# scHnRk_3.net
KiCad netlist of a schematic drawn in EAGLE
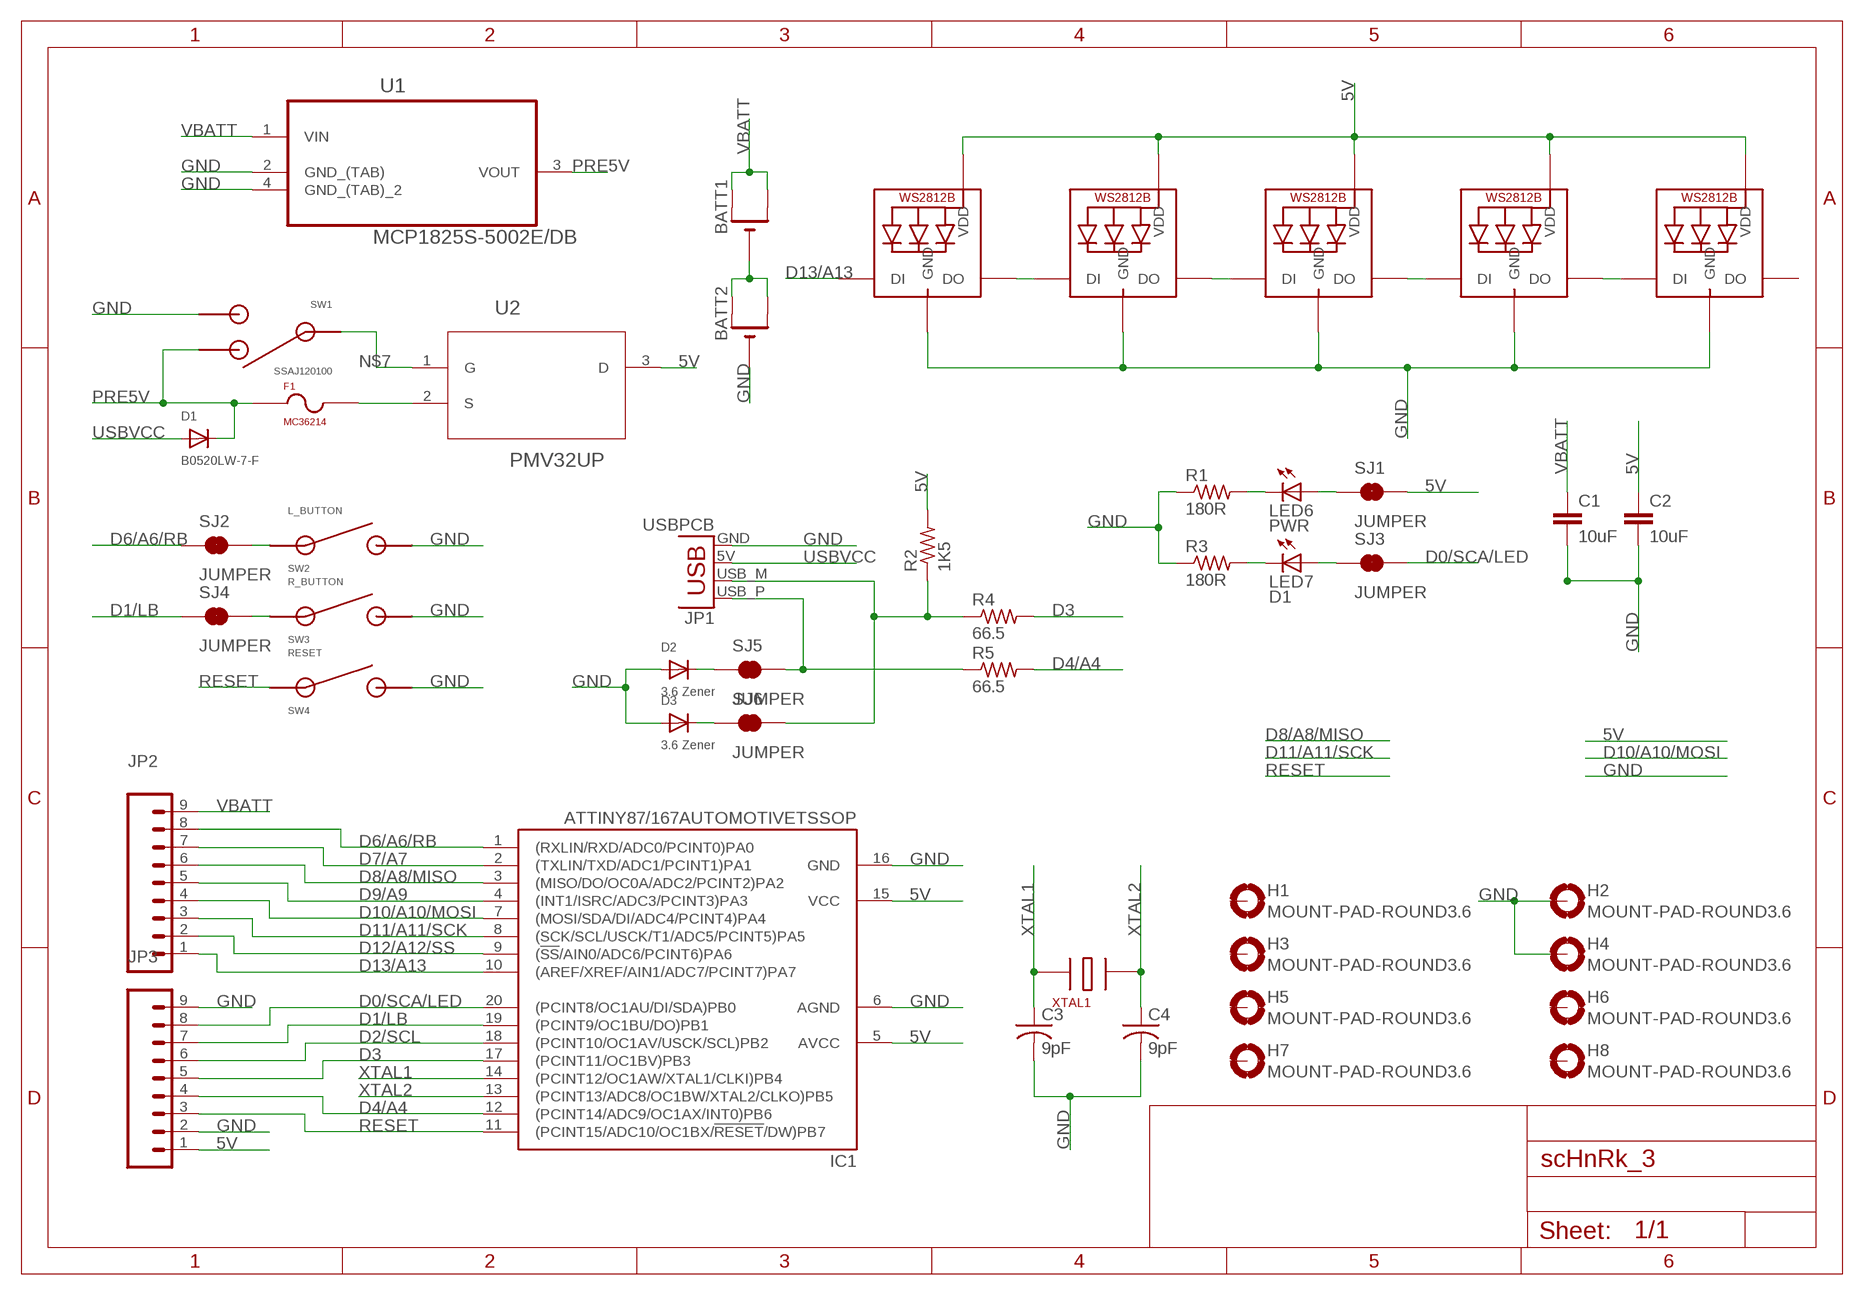
[diagram p0: schematic, sheet 1]

(export (version "E")
  (design (tool "Eeschema 10.0.6"))
  (components
    (comp (ref "BATT1")
      (value "CR2032SMT")
      (footprint "eagle-import:CR2032-SMD")
      (libsource (lib "eagle-import") (part "CR2032SMT"))
    )
    (comp (ref "BATT2")
      (value "CR2032SMT")
      (footprint "eagle-import:CR2032-SMD")
      (libsource (lib "eagle-import") (part "CR2032SMT"))
    )
    (comp (ref "C1")
      (value "10uF")
      (footprint "eagle-import:0805")
      (libsource (lib "eagle-import") (part "CAP0805"))
    )
    (comp (ref "C2")
      (value "10uF")
      (footprint "eagle-import:0805")
      (libsource (lib "eagle-import") (part "CAP0805"))
    )
    (comp (ref "C3")
      (value "9pF")
      (footprint "eagle-import:C0603K")
      (libsource (lib "eagle-import") (part "C-USC0603K"))
    )
    (comp (ref "C4")
      (value "9pF")
      (footprint "eagle-import:C0603K")
      (libsource (lib "eagle-import") (part "C-USC0603K"))
    )
    (comp (ref "D1")
      (value "B0520LW-7-F")
      (footprint "eagle-import:SOD-123")
      (libsource (lib "eagle-import") (part "DIODESOD-123"))
    )
    (comp (ref "D2")
      (value "3.6 Zener")
      (footprint "eagle-import:SOD-523")
      (libsource (lib "eagle-import") (part "DIODESOD-523"))
    )
    (comp (ref "D3")
      (value "3.6 Zener")
      (footprint "eagle-import:SOD-523")
      (libsource (lib "eagle-import") (part "DIODESOD-523"))
    )
    (comp (ref "F1")
      (value "MC36214")
      (footprint "eagle-import:MC36214")
      (libsource (lib "eagle-import") (part "MC36214"))
    )
    (comp (ref "H1")
      (value "MOUNT-PAD-ROUND3.6")
      (footprint "eagle-import:3,6-PAD")
      (libsource (lib "eagle-import") (part "MOUNT-PAD-ROUND3.6"))
    )
    (comp (ref "H2")
      (value "MOUNT-PAD-ROUND3.6")
      (footprint "eagle-import:3,6-PAD")
      (libsource (lib "eagle-import") (part "MOUNT-PAD-ROUND3.6"))
    )
    (comp (ref "H3")
      (value "MOUNT-PAD-ROUND3.6")
      (footprint "eagle-import:3,6-PAD")
      (libsource (lib "eagle-import") (part "MOUNT-PAD-ROUND3.6"))
    )
    (comp (ref "H4")
      (value "MOUNT-PAD-ROUND3.6")
      (footprint "eagle-import:3,6-PAD")
      (libsource (lib "eagle-import") (part "MOUNT-PAD-ROUND3.6"))
    )
    (comp (ref "H5")
      (value "MOUNT-PAD-ROUND3.6")
      (footprint "eagle-import:3,6-PAD")
      (libsource (lib "eagle-import") (part "MOUNT-PAD-ROUND3.6"))
    )
    (comp (ref "H6")
      (value "MOUNT-PAD-ROUND3.6")
      (footprint "eagle-import:3,6-PAD")
      (libsource (lib "eagle-import") (part "MOUNT-PAD-ROUND3.6"))
    )
    (comp (ref "H7")
      (value "MOUNT-PAD-ROUND3.6")
      (footprint "eagle-import:3,6-PAD")
      (libsource (lib "eagle-import") (part "MOUNT-PAD-ROUND3.6"))
    )
    (comp (ref "H8")
      (value "MOUNT-PAD-ROUND3.6")
      (footprint "eagle-import:3,6-PAD")
      (libsource (lib "eagle-import") (part "MOUNT-PAD-ROUND3.6"))
    )
    (comp (ref "IC1")
      (value "ATTINY87/167AUTOMOTIVETSSOP")
      (footprint "eagle-import:TSSOP20")
      (libsource (lib "eagle-import") (part "ATTINY87/167AUTOMOTIVETSSOP"))
    )
    (comp (ref "JP1")
      (value "USBPCB")
      (footprint "eagle-import:USB-A-PCB")
      (libsource (lib "eagle-import") (part "USBPCB"))
    )
    (comp (ref "JP2")
      (value "M09")
      (footprint "eagle-import:1X09")
      (libsource (lib "eagle-import") (part "M09"))
    )
    (comp (ref "JP3")
      (value "M09")
      (footprint "eagle-import:1X09")
      (libsource (lib "eagle-import") (part "M09"))
    )
    (comp (ref "LED1")
      (value "WS2812B5050")
      (footprint "eagle-import:WS2812B")
      (libsource (lib "eagle-import") (part "WS2812B5050"))
    )
    (comp (ref "LED2")
      (value "WS2812B5050")
      (footprint "eagle-import:WS2812B")
      (libsource (lib "eagle-import") (part "WS2812B5050"))
    )
    (comp (ref "LED3")
      (value "WS2812B5050")
      (footprint "eagle-import:WS2812B")
      (libsource (lib "eagle-import") (part "WS2812B5050"))
    )
    (comp (ref "LED4")
      (value "WS2812B5050")
      (footprint "eagle-import:WS2812B")
      (libsource (lib "eagle-import") (part "WS2812B5050"))
    )
    (comp (ref "LED5")
      (value "WS2812B5050")
      (footprint "eagle-import:WS2812B")
      (libsource (lib "eagle-import") (part "WS2812B5050"))
    )
    (comp (ref "LED6")
      (value "PWR")
      (footprint "eagle-import:CHIPLED_0603")
      (libsource (lib "eagle-import") (part "LEDCHIPLED_0603"))
    )
    (comp (ref "LED7")
      (value "D1")
      (footprint "eagle-import:CHIPLED_0603")
      (libsource (lib "eagle-import") (part "LEDCHIPLED_0603"))
    )
    (comp (ref "R1")
      (value "180R")
      (footprint "eagle-import:R0603")
      (libsource (lib "eagle-import") (part "R-US_R0603"))
    )
    (comp (ref "R2")
      (value "1K5")
      (footprint "eagle-import:R0603")
      (libsource (lib "eagle-import") (part "R-US_R0603"))
    )
    (comp (ref "R3")
      (value "180R")
      (footprint "eagle-import:R0603")
      (libsource (lib "eagle-import") (part "R-US_R0603"))
    )
    (comp (ref "R4")
      (value "66.5")
      (footprint "eagle-import:R0603")
      (libsource (lib "eagle-import") (part "R-US_R0603"))
    )
    (comp (ref "R5")
      (value "66.5")
      (footprint "eagle-import:R0603")
      (libsource (lib "eagle-import") (part "R-US_R0603"))
    )
    (comp (ref "SJ1")
      (value "JUMPER")
      (footprint "eagle-import:PAD-JUMPER-2-NC_BY_TRACE_YES_SILK")
      (libsource (lib "eagle-import") (part "JUMPER-PAD-2-NC_BY_TRACE"))
    )
    (comp (ref "SJ2")
      (value "JUMPER")
      (footprint "eagle-import:PAD-JUMPER-2-NC_BY_TRACE_YES_SILK")
      (libsource (lib "eagle-import") (part "JUMPER-PAD-2-NC_BY_TRACE"))
    )
    (comp (ref "SJ3")
      (value "JUMPER")
      (footprint "eagle-import:PAD-JUMPER-2-NC_BY_TRACE_YES_SILK")
      (libsource (lib "eagle-import") (part "JUMPER-PAD-2-NC_BY_TRACE"))
    )
    (comp (ref "SJ4")
      (value "JUMPER")
      (footprint "eagle-import:PAD-JUMPER-2-NC_BY_TRACE_YES_SILK")
      (libsource (lib "eagle-import") (part "JUMPER-PAD-2-NC_BY_TRACE"))
    )
    (comp (ref "SJ5")
      (value "JUMPER")
      (footprint "eagle-import:PAD-JUMPER-2-NC_BY_TRACE_YES_SILK")
      (libsource (lib "eagle-import") (part "JUMPER-PAD-2-NC_BY_TRACE"))
    )
    (comp (ref "SJ6")
      (value "JUMPER")
      (footprint "eagle-import:PAD-JUMPER-2-NC_BY_TRACE_YES_SILK")
      (libsource (lib "eagle-import") (part "JUMPER-PAD-2-NC_BY_TRACE"))
    )
    (comp (ref "SW1")
      (value "SSAJ120100")
      (footprint "eagle-import:SSAJ120100")
      (libsource (lib "eagle-import") (part "SSAJ120100"))
    )
    (comp (ref "SW2")
      (value "L_BUTTON")
      (footprint "eagle-import:SKRBAGE010")
      (libsource (lib "eagle-import") (part "SKRBAGE010"))
    )
    (comp (ref "SW3")
      (value "R_BUTTON")
      (footprint "eagle-import:SKRBAGE010")
      (libsource (lib "eagle-import") (part "SKRBAGE010"))
    )
    (comp (ref "SW4")
      (value "RESET")
      (footprint "eagle-import:SKRBAGE010")
      (libsource (lib "eagle-import") (part "SKRBAGE010"))
    )
    (comp (ref "U1")
      (value "MCP1825S-5002E/DB")
      (footprint "eagle-import:SOT230P700X180-4N")
      (libsource (lib "eagle-import") (part "MCP1825S-5002E/DB"))
    )
    (comp (ref "U2")
      (value "PMV32UP")
      (footprint "eagle-import:SOT95P230X110-3N")
      (libsource (lib "eagle-import") (part "PMV32UP"))
    )
    (comp (ref "XTAL1")
      (value "16MHZ-2467444")
      (footprint "eagle-import:16MHZ-2467444")
      (libsource (lib "eagle-import") (part "16MHZ-2467444"))
    )
  )
  (nets
    (net (code "1") (name "/5V") (class "Default")
      (node (ref "C2") (pin "1") (pinfunction "1_1") (pintype "passive"))
      (node (ref "IC1") (pin "15") (pinfunction "VCC_15") (pintype "power_in"))
      (node (ref "IC1") (pin "5") (pinfunction "AVCC_5") (pintype "bidirectional"))
      (node (ref "JP3") (pin "1") (pinfunction "1_1") (pintype "passive"))
      (node (ref "LED1") (pin "1-VDD") (pinfunction "VDD_1-VDD") (pintype "power_in"))
      (node (ref "LED2") (pin "1-VDD") (pinfunction "VDD_1-VDD") (pintype "power_in"))
      (node (ref "LED3") (pin "1-VDD") (pinfunction "VDD_1-VDD") (pintype "power_in"))
      (node (ref "LED4") (pin "1-VDD") (pinfunction "VDD_1-VDD") (pintype "power_in"))
      (node (ref "LED5") (pin "1-VDD") (pinfunction "VDD_1-VDD") (pintype "power_in"))
      (node (ref "R2") (pin "2") (pinfunction "2_2") (pintype "passive"))
      (node (ref "SJ1") (pin "2") (pinfunction "2_2") (pintype "passive"))
      (node (ref "U2") (pin "3") (pinfunction "D_3") (pintype "passive"))
    )
    (net (code "2") (name "/D0{slash}SCA{slash}LED") (class "Default")
      (node (ref "IC1") (pin "20") (pinfunction "(PCINT8/OC1AU/DI/SDA)PB0_20") (pintype "bidirectional"))
      (node (ref "JP3") (pin "8") (pinfunction "8_8") (pintype "passive"))
      (node (ref "SJ3") (pin "2") (pinfunction "2_2") (pintype "passive"))
    )
    (net (code "3") (name "/D1{slash}LB") (class "Default")
      (node (ref "IC1") (pin "19") (pinfunction "(PCINT9/OC1BU/DO)PB1_19") (pintype "bidirectional"))
      (node (ref "JP3") (pin "7") (pinfunction "7_7") (pintype "passive"))
      (node (ref "SJ4") (pin "1") (pinfunction "1_1") (pintype "passive"))
    )
    (net (code "4") (name "/D2{slash}SCL") (class "Default")
      (node (ref "IC1") (pin "18") (pinfunction "(PCINT10/OC1AV/USCK/SCL)PB2_18") (pintype "bidirectional"))
      (node (ref "JP3") (pin "6") (pinfunction "6_6") (pintype "passive"))
    )
    (net (code "5") (name "/D3") (class "Default")
      (node (ref "IC1") (pin "17") (pinfunction "(PCINT11/OC1BV)PB3_17") (pintype "bidirectional"))
      (node (ref "JP3") (pin "5") (pinfunction "5_5") (pintype "passive"))
      (node (ref "R4") (pin "2") (pinfunction "2_2") (pintype "passive"))
    )
    (net (code "6") (name "/D4{slash}A4") (class "Default")
      (node (ref "IC1") (pin "12") (pinfunction "(PCINT14/ADC9/OC1AX/INT0)PB6_12") (pintype "bidirectional"))
      (node (ref "JP3") (pin "4") (pinfunction "4_4") (pintype "passive"))
      (node (ref "R5") (pin "2") (pinfunction "2_2") (pintype "passive"))
    )
    (net (code "7") (name "/D6{slash}A6{slash}RB") (class "Default")
      (node (ref "IC1") (pin "1") (pinfunction "(RXLIN/RXD/ADC0/PCINT0)PA0_1") (pintype "bidirectional"))
      (node (ref "JP2") (pin "8") (pinfunction "8_8") (pintype "passive"))
      (node (ref "SJ2") (pin "1") (pinfunction "1_1") (pintype "passive"))
    )
    (net (code "8") (name "/D7{slash}A7") (class "Default")
      (node (ref "IC1") (pin "2") (pinfunction "(TXLIN/TXD/ADC1/PCINT1)PA1_2") (pintype "bidirectional"))
      (node (ref "JP2") (pin "7") (pinfunction "7_7") (pintype "passive"))
    )
    (net (code "9") (name "/D8{slash}A8{slash}MISO") (class "Default")
      (node (ref "IC1") (pin "3") (pinfunction "(MISO/DO/OC0A/ADC2/PCINT2)PA2_3") (pintype "bidirectional"))
      (node (ref "JP2") (pin "6") (pinfunction "6_6") (pintype "passive"))
    )
    (net (code "10") (name "/D9{slash}A9") (class "Default")
      (node (ref "IC1") (pin "4") (pinfunction "(INT1/ISRC/ADC3/PCINT3)PA3_4") (pintype "bidirectional"))
      (node (ref "JP2") (pin "5") (pinfunction "5_5") (pintype "passive"))
    )
    (net (code "11") (name "/D10{slash}A10{slash}MOSI") (class "Default")
      (node (ref "IC1") (pin "7") (pinfunction "(MOSI/SDA/DI/ADC4/PCINT4)PA4_7") (pintype "bidirectional"))
      (node (ref "JP2") (pin "4") (pinfunction "4_4") (pintype "passive"))
    )
    (net (code "12") (name "/D11{slash}A11{slash}SCK") (class "Default")
      (node (ref "IC1") (pin "8") (pinfunction "(SCK/SCL/USCK/T1/ADC5/PCINT5)PA5_8") (pintype "bidirectional"))
      (node (ref "JP2") (pin "3") (pinfunction "3_3") (pintype "passive"))
    )
    (net (code "13") (name "/D12{slash}A12{slash}SS") (class "Default")
      (node (ref "IC1") (pin "9") (pinfunction "(~{SS}/AIN0/ADC6/PCINT6)PA6_9") (pintype "bidirectional"))
      (node (ref "JP2") (pin "2") (pinfunction "2_2") (pintype "passive"))
    )
    (net (code "14") (name "/D13{slash}A13") (class "Default")
      (node (ref "IC1") (pin "10") (pinfunction "(AREF/XREF/AIN1/ADC7/PCINT7)PA7_10") (pintype "bidirectional"))
      (node (ref "JP2") (pin "1") (pinfunction "1_1") (pintype "passive"))
      (node (ref "LED1") (pin "4-DIN") (pinfunction "DI_4-DIN") (pintype "input"))
    )
    (net (code "15") (name "/GND") (class "Default")
      (node (ref "BATT2") (pin "-") (pinfunction "-_-") (pintype "passive"))
      (node (ref "C1") (pin "2") (pinfunction "2_2") (pintype "passive"))
      (node (ref "C2") (pin "2") (pinfunction "2_2") (pintype "passive"))
      (node (ref "C3") (pin "2") (pinfunction "2_2") (pintype "passive"))
      (node (ref "C4") (pin "2") (pinfunction "2_2") (pintype "passive"))
      (node (ref "D2") (pin "A") (pinfunction "A_A") (pintype "passive"))
      (node (ref "D3") (pin "A") (pinfunction "A_A") (pintype "passive"))
      (node (ref "H2") (pin "B3,6") (pinfunction "MOUNT_B3,6") (pintype "passive"))
      (node (ref "H4") (pin "B3,6") (pinfunction "MOUNT_B3,6") (pintype "passive"))
      (node (ref "IC1") (pin "16") (pinfunction "GND_16") (pintype "power_in"))
      (node (ref "IC1") (pin "6") (pinfunction "AGND_6") (pintype "bidirectional"))
      (node (ref "JP1") (pin "GND") (pinfunction "GND_GND") (pintype "bidirectional"))
      (node (ref "JP3") (pin "2") (pinfunction "2_2") (pintype "passive"))
      (node (ref "JP3") (pin "9") (pinfunction "9_9") (pintype "passive"))
      (node (ref "LED1") (pin "3-GND") (pinfunction "GND_3-GND") (pintype "power_in"))
      (node (ref "LED2") (pin "3-GND") (pinfunction "GND_3-GND") (pintype "power_in"))
      (node (ref "LED3") (pin "3-GND") (pinfunction "GND_3-GND") (pintype "power_in"))
      (node (ref "LED4") (pin "3-GND") (pinfunction "GND_3-GND") (pintype "power_in"))
      (node (ref "LED5") (pin "3-GND") (pinfunction "GND_3-GND") (pintype "power_in"))
      (node (ref "R1") (pin "1") (pinfunction "1_1") (pintype "passive"))
      (node (ref "R3") (pin "1") (pinfunction "1_1") (pintype "passive"))
      (node (ref "SW1") (pin "P$2") (pinfunction "P$2_P$2") (pintype "bidirectional"))
      (node (ref "SW2") (pin "P$2") (pinfunction "P$2_P$2") (pintype "bidirectional"))
      (node (ref "SW2") (pin "P$4") (pinfunction "P$2_P$4") (pintype "bidirectional"))
      (node (ref "SW3") (pin "P$2") (pinfunction "P$2_P$2") (pintype "bidirectional"))
      (node (ref "SW3") (pin "P$4") (pinfunction "P$2_P$4") (pintype "bidirectional"))
      (node (ref "SW4") (pin "P$2") (pinfunction "P$2_P$2") (pintype "bidirectional"))
      (node (ref "SW4") (pin "P$4") (pinfunction "P$2_P$4") (pintype "bidirectional"))
      (node (ref "U1") (pin "2") (pinfunction "GND_(TAB)_2") (pintype "passive"))
      (node (ref "U1") (pin "4") (pinfunction "GND_(TAB)_2_4") (pintype "passive"))
    )
    (net (code "16") (name "/N$7") (class "Default")
      (node (ref "SW1") (pin "P$C") (pinfunction "P$C_P$C") (pintype "bidirectional"))
      (node (ref "U2") (pin "1") (pinfunction "G_1") (pintype "passive"))
    )
    (net (code "17") (name "/PRE5V") (class "Default")
      (node (ref "D1") (pin "C") (pinfunction "C_C") (pintype "passive"))
      (node (ref "F1") (pin "P$1") (pinfunction "P$1_P$1") (pintype "bidirectional"))
      (node (ref "SW1") (pin "P$1") (pinfunction "P$1_P$1") (pintype "bidirectional"))
      (node (ref "U1") (pin "3") (pinfunction "VOUT_3") (pintype "output"))
    )
    (net (code "18") (name "/RESET") (class "Default")
      (node (ref "IC1") (pin "11") (pinfunction "(PCINT15/ADC10/OC1BX/~{RESET}/DW)PB7_11") (pintype "bidirectional"))
      (node (ref "JP3") (pin "3") (pinfunction "3_3") (pintype "passive"))
      (node (ref "SW4") (pin "P$1") (pinfunction "P$1_P$1") (pintype "bidirectional"))
      (node (ref "SW4") (pin "P$3") (pinfunction "P$1_P$3") (pintype "bidirectional"))
    )
    (net (code "19") (name "/USBVCC") (class "Default")
      (node (ref "D1") (pin "A") (pinfunction "A_A") (pintype "passive"))
      (node (ref "JP1") (pin "5V") (pinfunction "VBUS_5V") (pintype "bidirectional"))
    )
    (net (code "20") (name "/VBATT") (class "Default")
      (node (ref "BATT1") (pin "+$1") (pinfunction "+_+$1") (pintype "passive"))
      (node (ref "BATT1") (pin "+$2") (pinfunction "+1_+$2") (pintype "passive"))
      (node (ref "C1") (pin "1") (pinfunction "1_1") (pintype "passive"))
      (node (ref "JP2") (pin "9") (pinfunction "9_9") (pintype "passive"))
      (node (ref "U1") (pin "1") (pinfunction "VIN_1") (pintype "input"))
    )
    (net (code "21") (name "/XTAL1") (class "Default")
      (node (ref "C3") (pin "1") (pinfunction "1_1") (pintype "passive"))
      (node (ref "IC1") (pin "14") (pinfunction "(PCINT12/OC1AW/XTAL1/CLKI)PB4_14") (pintype "bidirectional"))
      (node (ref "XTAL1") (pin "P$1") (pinfunction "P$1_P$1") (pintype "bidirectional"))
    )
    (net (code "22") (name "/XTAL2") (class "Default")
      (node (ref "C4") (pin "1") (pinfunction "1_1") (pintype "passive"))
      (node (ref "IC1") (pin "13") (pinfunction "(PCINT13/ADC8/OC1BW/XTAL2/CLKO)PB5_13") (pintype "bidirectional"))
      (node (ref "XTAL1") (pin "P$3") (pinfunction "P$2_P$3") (pintype "bidirectional"))
    )
    (net (code "23") (name "Net-(BATT2-+)") (class "Default")
      (node (ref "BATT1") (pin "-") (pinfunction "-_-") (pintype "passive"))
      (node (ref "BATT2") (pin "+$1") (pinfunction "+_+$1") (pintype "passive"))
      (node (ref "BATT2") (pin "+$2") (pinfunction "+1_+$2") (pintype "passive"))
    )
    (net (code "24") (name "Net-(D2-C)") (class "Default")
      (node (ref "D2") (pin "K") (pinfunction "C_K") (pintype "passive"))
      (node (ref "SJ5") (pin "1") (pinfunction "1_1") (pintype "passive"))
    )
    (net (code "25") (name "Net-(D3-C)") (class "Default")
      (node (ref "D3") (pin "K") (pinfunction "C_K") (pintype "passive"))
      (node (ref "SJ6") (pin "1") (pinfunction "1_1") (pintype "passive"))
    )
    (net (code "26") (name "Net-(JP1-D+)") (class "Default")
      (node (ref "JP1") (pin "USB_P") (pinfunction "D+_USB_P") (pintype "bidirectional"))
      (node (ref "R5") (pin "1") (pinfunction "1_1") (pintype "passive"))
      (node (ref "SJ5") (pin "2") (pinfunction "2_2") (pintype "passive"))
    )
    (net (code "27") (name "Net-(JP1-D-)") (class "Default")
      (node (ref "JP1") (pin "USB_M") (pinfunction "D-_USB_M") (pintype "bidirectional"))
      (node (ref "R2") (pin "1") (pinfunction "1_1") (pintype "passive"))
      (node (ref "R4") (pin "1") (pinfunction "1_1") (pintype "passive"))
      (node (ref "SJ6") (pin "2") (pinfunction "2_2") (pintype "passive"))
    )
    (net (code "28") (name "Net-(LED1-DO)") (class "Default")
      (node (ref "LED1") (pin "2-DOUT") (pinfunction "DO_2-DOUT") (pintype "output"))
      (node (ref "LED2") (pin "4-DIN") (pinfunction "DI_4-DIN") (pintype "input"))
    )
    (net (code "29") (name "Net-(LED2-DO)") (class "Default")
      (node (ref "LED2") (pin "2-DOUT") (pinfunction "DO_2-DOUT") (pintype "output"))
      (node (ref "LED3") (pin "4-DIN") (pinfunction "DI_4-DIN") (pintype "input"))
    )
    (net (code "30") (name "Net-(LED3-DO)") (class "Default")
      (node (ref "LED3") (pin "2-DOUT") (pinfunction "DO_2-DOUT") (pintype "output"))
      (node (ref "LED4") (pin "4-DIN") (pinfunction "DI_4-DIN") (pintype "input"))
    )
    (net (code "31") (name "Net-(LED4-DO)") (class "Default")
      (node (ref "LED4") (pin "2-DOUT") (pinfunction "DO_2-DOUT") (pintype "output"))
      (node (ref "LED5") (pin "4-DIN") (pinfunction "DI_4-DIN") (pintype "input"))
    )
    (net (code "32") (name "Net-(LED6-PadA)") (class "Default")
      (node (ref "LED6") (pin "A") (pinfunction "A_A") (pintype "passive"))
      (node (ref "SJ1") (pin "1") (pinfunction "1_1") (pintype "passive"))
    )
    (net (code "33") (name "Net-(LED6-PadC)") (class "Default")
      (node (ref "LED6") (pin "C") (pinfunction "C_C") (pintype "passive"))
      (node (ref "R1") (pin "2") (pinfunction "2_2") (pintype "passive"))
    )
    (net (code "34") (name "Net-(LED7-PadA)") (class "Default")
      (node (ref "LED7") (pin "A") (pinfunction "A_A") (pintype "passive"))
      (node (ref "SJ3") (pin "1") (pinfunction "1_1") (pintype "passive"))
    )
    (net (code "35") (name "Net-(LED7-PadC)") (class "Default")
      (node (ref "LED7") (pin "C") (pinfunction "C_C") (pintype "passive"))
      (node (ref "R3") (pin "2") (pinfunction "2_2") (pintype "passive"))
    )
    (net (code "36") (name "Net-(SJ2-Pad2)") (class "Default")
      (node (ref "SJ2") (pin "2") (pinfunction "2_2") (pintype "passive"))
      (node (ref "SW2") (pin "P$1") (pinfunction "P$1_P$1") (pintype "bidirectional"))
      (node (ref "SW2") (pin "P$3") (pinfunction "P$1_P$3") (pintype "bidirectional"))
    )
    (net (code "37") (name "Net-(SJ4-Pad2)") (class "Default")
      (node (ref "SJ4") (pin "2") (pinfunction "2_2") (pintype "passive"))
      (node (ref "SW3") (pin "P$1") (pinfunction "P$1_P$1") (pintype "bidirectional"))
      (node (ref "SW3") (pin "P$3") (pinfunction "P$1_P$3") (pintype "bidirectional"))
    )
    (net (code "38") (name "Net-(U2-S)") (class "Default")
      (node (ref "F1") (pin "P$2") (pinfunction "P$2_P$2") (pintype "bidirectional"))
      (node (ref "U2") (pin "2") (pinfunction "S_2") (pintype "passive"))
    )
    (net (code "39") (name "unconnected-(H1-MOUNT-PadB3,6)") (class "Default")
      (node (ref "H1") (pin "B3,6") (pinfunction "MOUNT_B3,6") (pintype "passive"))
    )
    (net (code "40") (name "unconnected-(H3-MOUNT-PadB3,6)") (class "Default")
      (node (ref "H3") (pin "B3,6") (pinfunction "MOUNT_B3,6") (pintype "passive"))
    )
    (net (code "41") (name "unconnected-(H5-MOUNT-PadB3,6)") (class "Default")
      (node (ref "H5") (pin "B3,6") (pinfunction "MOUNT_B3,6") (pintype "passive"))
    )
    (net (code "42") (name "unconnected-(H6-MOUNT-PadB3,6)") (class "Default")
      (node (ref "H6") (pin "B3,6") (pinfunction "MOUNT_B3,6") (pintype "passive"))
    )
    (net (code "43") (name "unconnected-(H7-MOUNT-PadB3,6)") (class "Default")
      (node (ref "H7") (pin "B3,6") (pinfunction "MOUNT_B3,6") (pintype "passive"))
    )
    (net (code "44") (name "unconnected-(H8-MOUNT-PadB3,6)") (class "Default")
      (node (ref "H8") (pin "B3,6") (pinfunction "MOUNT_B3,6") (pintype "passive"))
    )
    (net (code "45") (name "unconnected-(LED5-DO-Pad2-DOUT)") (class "Default")
      (node (ref "LED5") (pin "2-DOUT") (pinfunction "DO_2-DOUT") (pintype "output"))
    )
  )
)
